# edisonLightColor.net
KiCad netlist of a schematic drawn in EAGLE
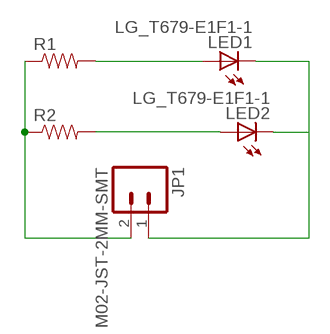
[diagram p0: schematic, sheet 1]

(export (version "E")
  (design (tool "Eeschema 10.0.6"))
  (components
    (comp (ref "JP1")
      (value "M02-JST-2MM-SMT")
      (footprint "eagle-import:JST-2-SMD")
      (libsource (lib "eagle-import") (part "M02-JST-2MM-SMT"))
    )
    (comp (ref "LED1")
      (value "LG_T679-E1F1-1")
      (footprint "eagle-import:PLCC2")
      (libsource (lib "eagle-import") (part "_T679-?-1E1F1LG"))
    )
    (comp (ref "LED2")
      (value "LG_T679-E1F1-1")
      (footprint "eagle-import:PLCC2")
      (libsource (lib "eagle-import") (part "_T679-?-1E1F1LG"))
    )
    (comp (ref "R1")
      (value "RESISTOR0805-RES")
      (footprint "eagle-import:0805")
      (libsource (lib "eagle-import") (part "RESISTOR0805-RES"))
    )
    (comp (ref "R2")
      (value "RESISTOR0805-RES")
      (footprint "eagle-import:0805")
      (libsource (lib "eagle-import") (part "RESISTOR0805-RES"))
    )
  )
  (nets
    (net (code "1") (name "Net-(JP1-1)") (class "Default")
      (node (ref "JP1") (pin "2") (pinfunction "1_2") (pintype "passive"))
      (node (ref "R1") (pin "1") (pinfunction "1_1") (pintype "passive"))
      (node (ref "R2") (pin "1") (pinfunction "1_1") (pintype "passive"))
    )
    (net (code "2") (name "Net-(JP1-2)") (class "Default")
      (node (ref "JP1") (pin "1") (pinfunction "2_1") (pintype "passive"))
      (node (ref "LED1") (pin "C") (pinfunction "C_C") (pintype "passive"))
      (node (ref "LED2") (pin "C") (pinfunction "C_C") (pintype "passive"))
    )
    (net (code "3") (name "Net-(LED1-PadA)") (class "Default")
      (node (ref "LED1") (pin "A") (pinfunction "A_A") (pintype "passive"))
      (node (ref "R1") (pin "2") (pinfunction "2_2") (pintype "passive"))
    )
    (net (code "4") (name "Net-(LED2-PadA)") (class "Default")
      (node (ref "LED2") (pin "A") (pinfunction "A_A") (pintype "passive"))
      (node (ref "R2") (pin "2") (pinfunction "2_2") (pintype "passive"))
    )
  )
)
